# PDB2.net
KiCad netlist of a schematic drawn in EAGLE
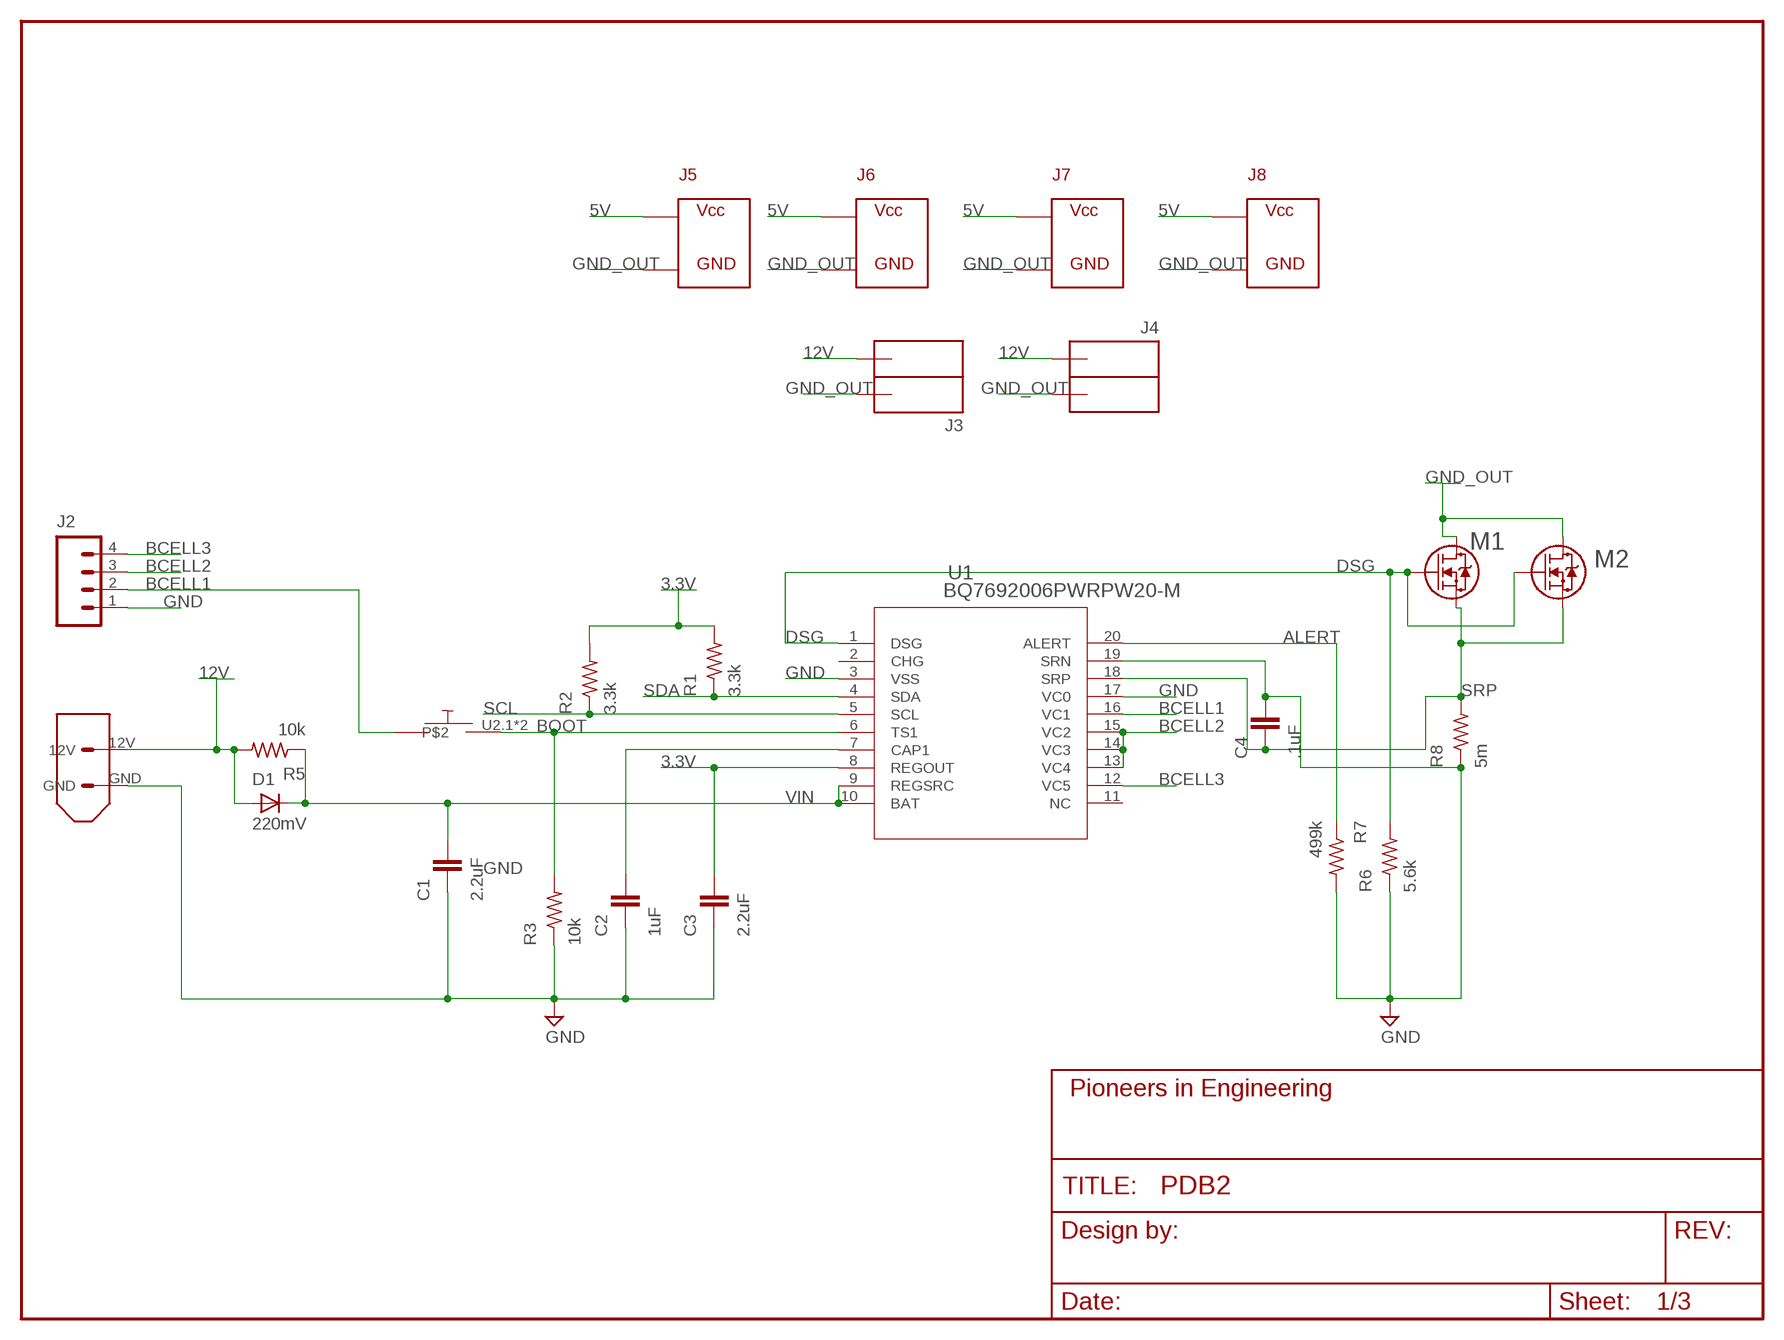
[diagram p0: schematic, sheet 1]
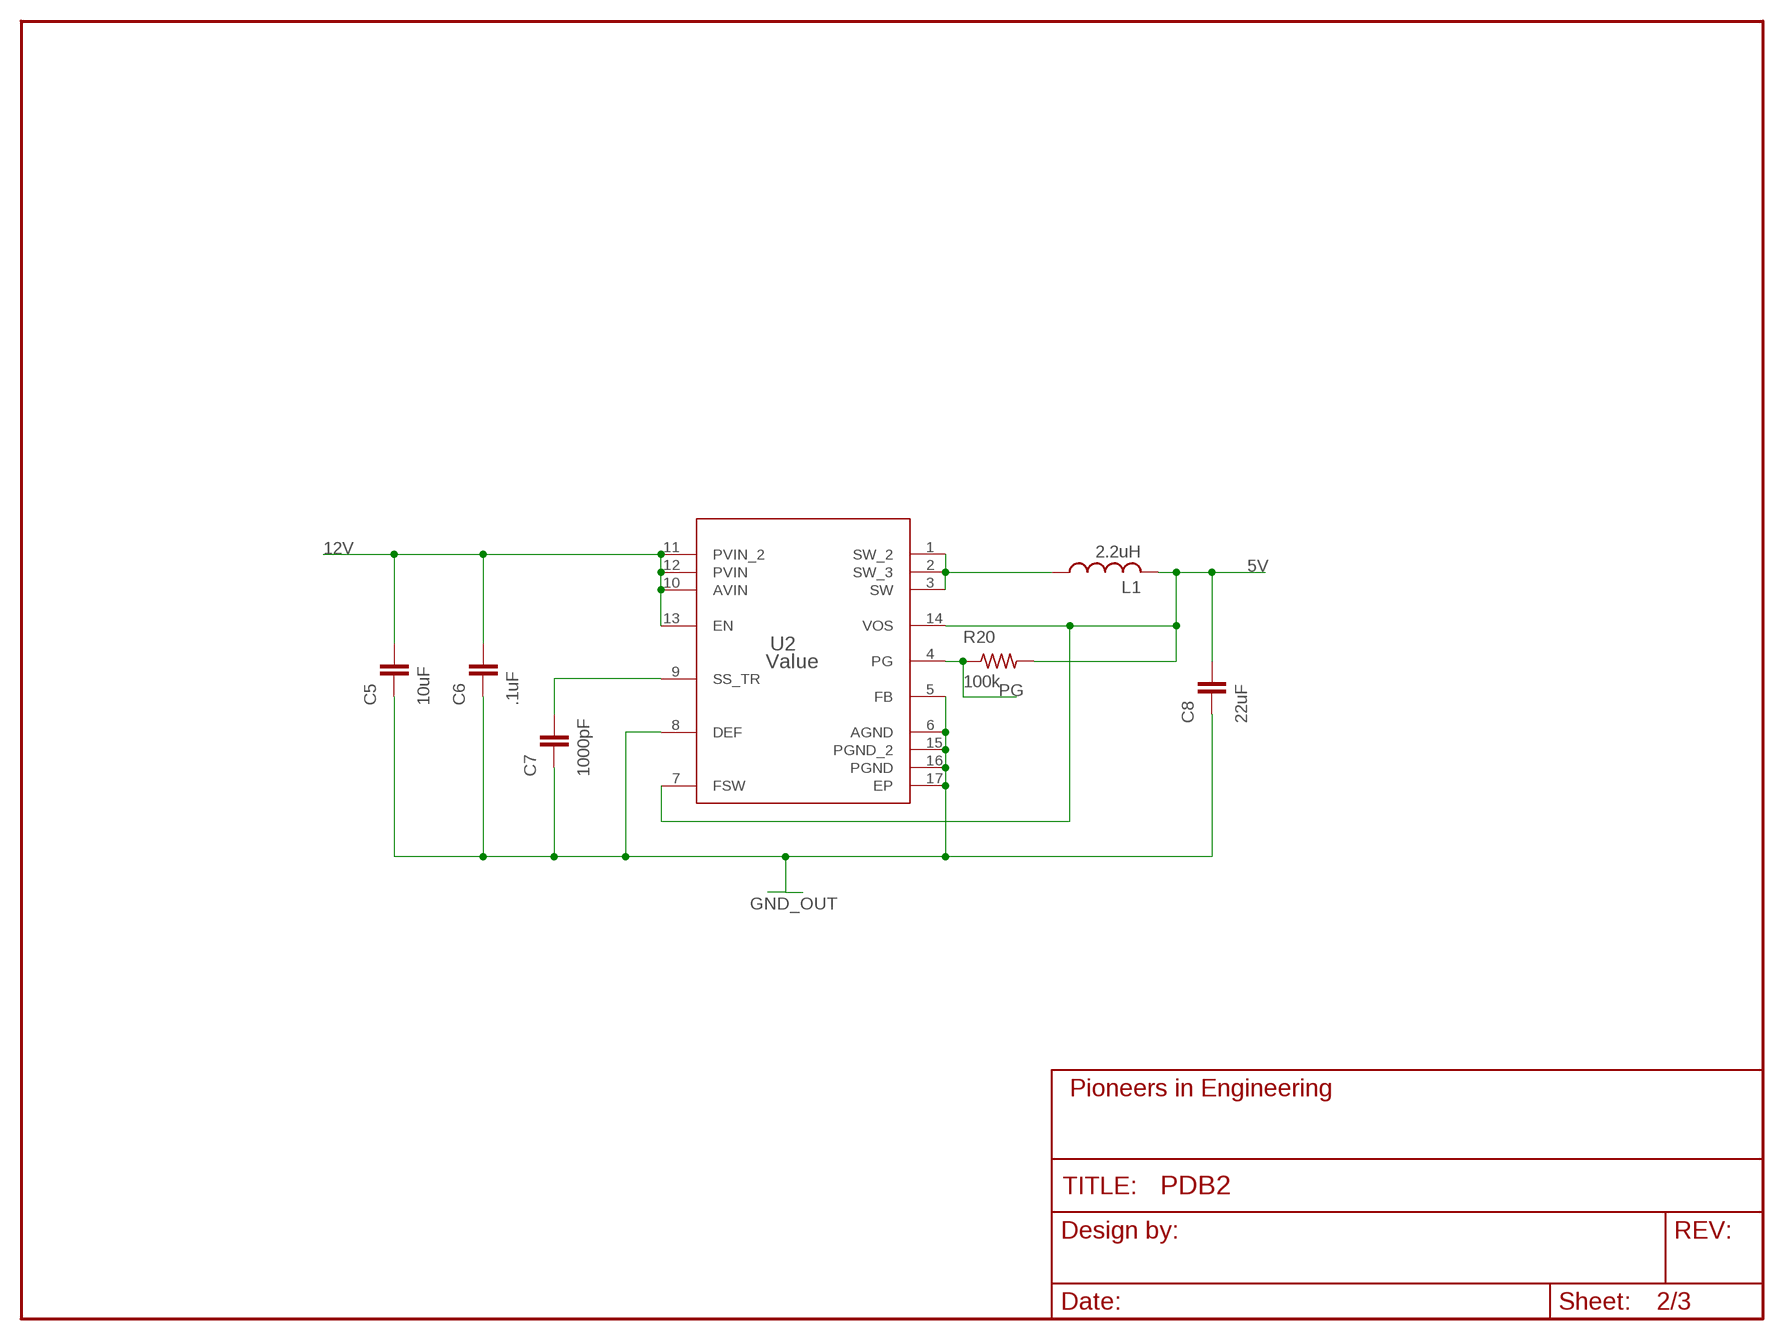
[diagram p1: schematic, sheet 2]
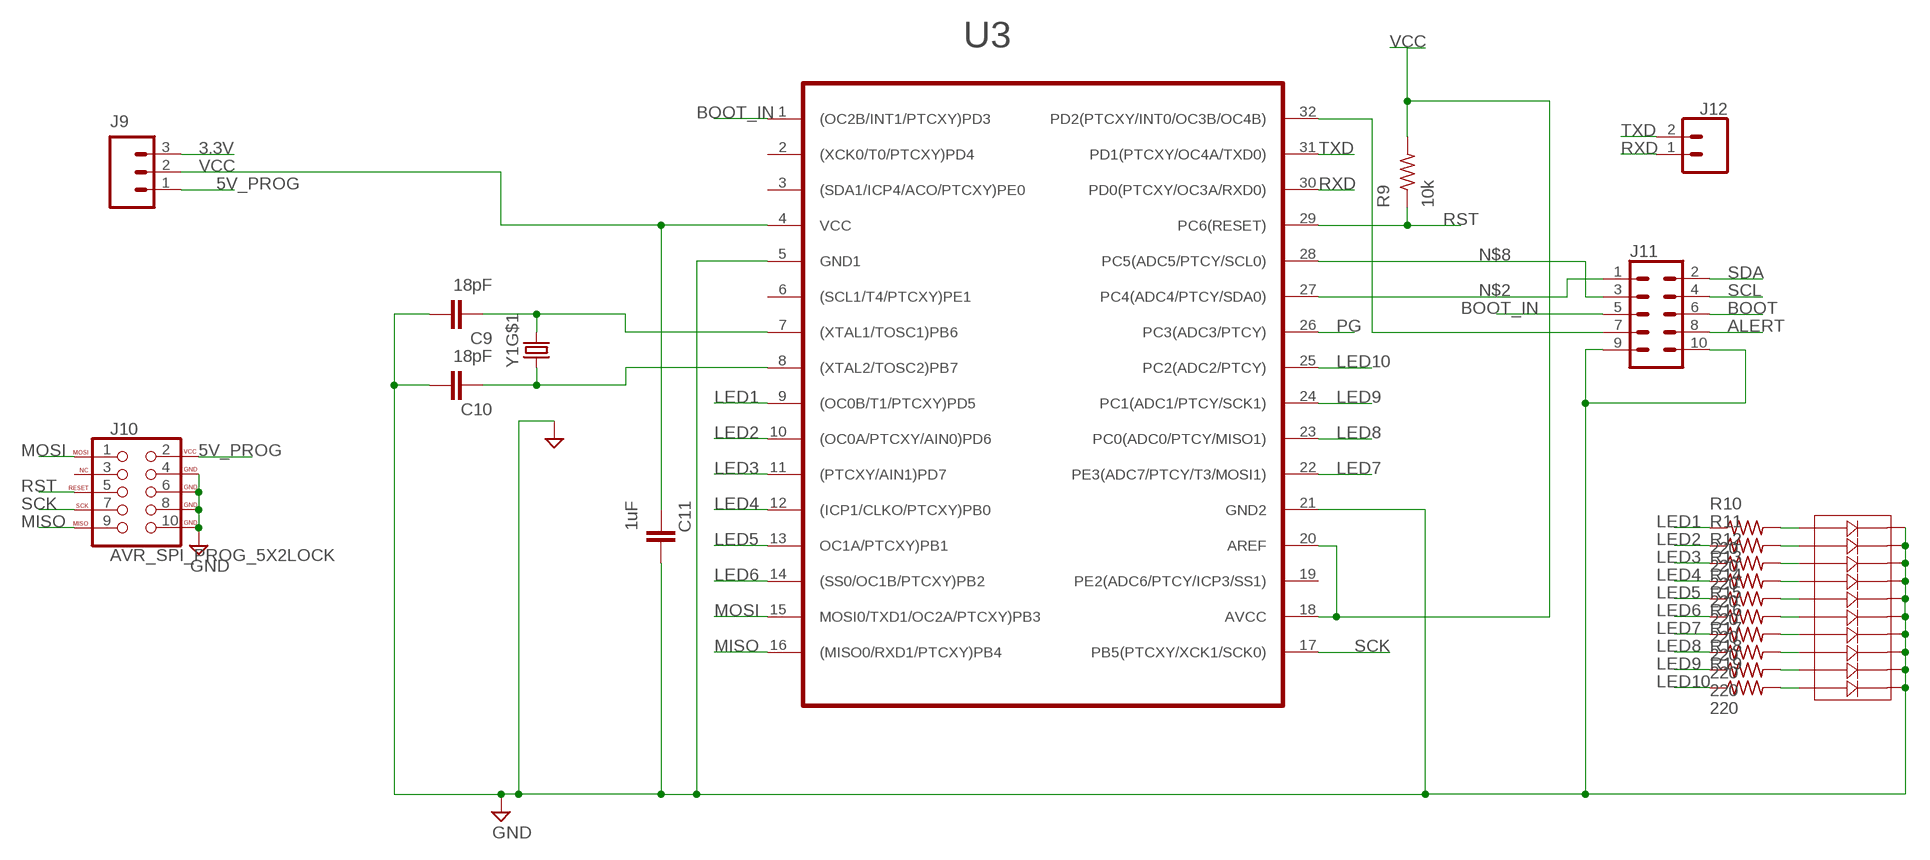
[diagram p2: schematic, sheet 3]

(export (version "E")
  (design (tool "Eeschema 10.0.6"))
  (components
    (comp (ref "BUT1")
      (value "D6C90F1LFS")
      (footprint "eagle-import:D6C_BUTTON")
      (libsource (lib "eagle-import") (part "D6C90F1LFS"))
    )
    (comp (ref "C1")
      (value "2.2uF")
      (footprint "eagle-import:0603-CAP")
      (libsource (lib "eagle-import") (part "CAP0603-CAP"))
    )
    (comp (ref "C2")
      (value "1uF")
      (footprint "eagle-import:0603-CAP")
      (libsource (lib "eagle-import") (part "CAP0603-CAP"))
    )
    (comp (ref "C3")
      (value "2.2uF")
      (footprint "eagle-import:0603-CAP")
      (libsource (lib "eagle-import") (part "CAP0603-CAP"))
    )
    (comp (ref "C4")
      (value ".1uF")
      (footprint "eagle-import:0603-CAP")
      (libsource (lib "eagle-import") (part "CAP0603-CAP"))
    )
    (comp (ref "D1")
      (value "220mV")
      (footprint "eagle-import:SOD-323")
      (libsource (lib "eagle-import") (part "DIODESOD-323"))
    )
    (comp (ref "J1")
      (value "XT60CONNECTOR")
      (footprint "eagle-import:XT60CONNECTOR")
      (fields (field (name "PARTNUMBER") "PRT-10474 "))
      (libsource (lib "eagle-import") (part "XT60CONNECTOR"))
    )
    (comp (ref "J2")
      (value "M041X04-MTA")
      (footprint "eagle-import:1X04-MTA")
      (libsource (lib "eagle-import") (part "M041X04-MTA"))
    )
    (comp (ref "J3")
      (value "ANDERSONVERTICAL")
      (footprint "eagle-import:ANDERSON_VERTICAL")
      (libsource (lib "eagle-import") (part "ANDERSONVERTICAL"))
    )
    (comp (ref "J4")
      (value "ANDERSONVERTICAL")
      (footprint "eagle-import:ANDERSON_VERTICAL")
      (libsource (lib "eagle-import") (part "ANDERSONVERTICAL"))
    )
    (comp (ref "J5")
      (value "ATX")
      (footprint "eagle-import:ATX")
      (libsource (lib "eagle-import") (part "ATX"))
    )
    (comp (ref "J6")
      (value "ATX")
      (footprint "eagle-import:ATX")
      (libsource (lib "eagle-import") (part "ATX"))
    )
    (comp (ref "J7")
      (value "ATX")
      (footprint "eagle-import:ATX")
      (libsource (lib "eagle-import") (part "ATX"))
    )
    (comp (ref "J8")
      (value "ATX")
      (footprint "eagle-import:ATX")
      (libsource (lib "eagle-import") (part "ATX"))
    )
    (comp (ref "M1")
      (value "STD20NF06LDPAK-M")
      (footprint "eagle-import:DPAK-M")
      (fields (field (name "MANUFACTURER_PART_NUMBER") "STD20NF06L"))
      (libsource (lib "eagle-import") (part "STD20NF06LDPAK-M"))
    )
    (comp (ref "M2")
      (value "STD20NF06LDPAK-M")
      (footprint "eagle-import:DPAK-M")
      (fields (field (name "MANUFACTURER_PART_NUMBER") "STD20NF06L"))
      (libsource (lib "eagle-import") (part "STD20NF06LDPAK-M"))
    )
    (comp (ref "R1")
      (value "3.3k")
      (footprint "eagle-import:R0603")
      (fields (field (name "MANUFACTURER") "Rohm Semiconductor"))
      (libsource (lib "eagle-import") (part "R-US_R0603"))
    )
    (comp (ref "R2")
      (value "3.3k")
      (footprint "eagle-import:R0603")
      (fields (field (name "MANUFACTURER") "Rohm Semiconductor"))
      (libsource (lib "eagle-import") (part "R-US_R0603"))
    )
    (comp (ref "R3")
      (value "10k")
      (footprint "eagle-import:R0603")
      (fields (field (name "MANUFACTURER") "Rohm Semiconductor"))
      (libsource (lib "eagle-import") (part "R-US_R0603"))
    )
    (comp (ref "R5")
      (value "10k")
      (footprint "eagle-import:R0603")
      (fields (field (name "MANUFACTURER") "Rohm Semiconductor"))
      (libsource (lib "eagle-import") (part "R-US_R0603"))
    )
    (comp (ref "R6")
      (value "5.6k")
      (footprint "eagle-import:R0603")
      (fields (field (name "MANUFACTURER") "Rohm Semiconductor"))
      (libsource (lib "eagle-import") (part "R-US_R0603"))
    )
    (comp (ref "R7")
      (value "499k")
      (footprint "eagle-import:R0603")
      (fields (field (name "MANUFACTURER") "Rohm Semiconductor"))
      (libsource (lib "eagle-import") (part "R-US_R0603"))
    )
    (comp (ref "R8")
      (value "5m")
      (footprint "eagle-import:SMD_SHUNT")
      (fields (field (name "MANUFACTURER_PART_NO") "WSHM28185L000FEA"))
      (libsource (lib "eagle-import") (part "SHUNT_SMD"))
    )
    (comp (ref "U1")
      (value "BQ7692006PWRPW20-M")
      (footprint "eagle-import:PW20-M")
      (fields (field (name "MANUFACTURER_PART_NUMBER") "BQ7692006PWR"))
      (libsource (lib "eagle-import") (part "BQ7692006PWRPW20-M"))
    )
    (comp (ref "C5")
      (value "10uF")
      (footprint "eagle-import:0805")
      (libsource (lib "eagle-import") (part "CAP0805"))
    )
    (comp (ref "C6")
      (value ".1uF")
      (footprint "eagle-import:0603-CAP")
      (libsource (lib "eagle-import") (part "CAP0603-CAP"))
    )
    (comp (ref "C7")
      (value "1000pF")
      (footprint "eagle-import:0603-CAP")
      (libsource (lib "eagle-import") (part "CAP0603-CAP"))
    )
    (comp (ref "C8")
      (value "22uF")
      (footprint "eagle-import:0805")
      (libsource (lib "eagle-import") (part "CAP0805"))
    )
    (comp (ref "L1")
      (value "2.2uH")
      (footprint "eagle-import:ASPI")
      (libsource (lib "eagle-import") (part "ASPI-0530_INDUCTOR"))
    )
    (comp (ref "R20")
      (value "100k")
      (footprint "eagle-import:R0603")
      (fields (field (name "MANUFACTURER") "Rohm Semiconductor"))
      (libsource (lib "eagle-import") (part "R-US_R0603"))
    )
    (comp (ref "U2")
      (value "Value")
      (footprint "eagle-import:RGT0016C")
      (fields
        (field (name "MANUFACTURER") "Texas Instruments")
        (field (name "MANUFACTURER_PART_NUMBER") "TPS62133RGTR")
      )
      (libsource (lib "eagle-import") (part "TPS62133RGTR"))
    )
    (comp (ref "C9")
      (value "18pF")
      (footprint "eagle-import:0603-CAP")
      (libsource (lib "eagle-import") (part "CAP0603-CAP"))
    )
    (comp (ref "C10")
      (value "18pF")
      (footprint "eagle-import:0603-CAP")
      (libsource (lib "eagle-import") (part "CAP0603-CAP"))
    )
    (comp (ref "C11")
      (value "1uF")
      (footprint "eagle-import:0603-CAP")
      (libsource (lib "eagle-import") (part "CAP0603-CAP"))
    )
    (comp (ref "J9")
      (value "M03PTH")
      (footprint "eagle-import:1X03")
      (libsource (lib "eagle-import") (part "M03PTH"))
    )
    (comp (ref "J10")
      (value "AVR_SPI_PROG_5X2LOCK")
      (footprint "eagle-import:2X5-SHROUDED_LOCK")
      (libsource (lib "eagle-import") (part "AVR_SPI_PROG_5X2LOCK"))
    )
    (comp (ref "J11")
      (value "CONN_05X2NO_SILK")
      (footprint "eagle-import:2X5_NOSILK")
      (libsource (lib "eagle-import") (part "CONN_05X2NO_SILK"))
    )
    (comp (ref "J12")
      (value "CONN_02")
      (footprint "eagle-import:1X02")
      (libsource (lib "eagle-import") (part "CONN_02"))
    )
    (comp (ref "LED1")
      (value "BAR_SEGMENT_DISPLAY")
      (footprint "eagle-import:BAR_SEGMENT_DISPLAY")
      (libsource (lib "eagle-import") (part "BAR_SEGMENT_DISPLAY"))
    )
    (comp (ref "R9")
      (value "10k")
      (footprint "eagle-import:R0603")
      (fields (field (name "MANUFACTURER") "Rohm Semiconductor"))
      (libsource (lib "eagle-import") (part "R-US_R0603"))
    )
    (comp (ref "R10")
      (value "220")
      (footprint "eagle-import:R0603")
      (fields (field (name "MANUFACTURER") "Rohm Semiconductor"))
      (libsource (lib "eagle-import") (part "R-US_R0603"))
    )
    (comp (ref "R11")
      (value "220")
      (footprint "eagle-import:R0603")
      (fields (field (name "MANUFACTURER") "Rohm Semiconductor"))
      (libsource (lib "eagle-import") (part "R-US_R0603"))
    )
    (comp (ref "R12")
      (value "220")
      (footprint "eagle-import:R0603")
      (fields (field (name "MANUFACTURER") "Rohm Semiconductor"))
      (libsource (lib "eagle-import") (part "R-US_R0603"))
    )
    (comp (ref "R13")
      (value "220")
      (footprint "eagle-import:R0603")
      (fields (field (name "MANUFACTURER") "Rohm Semiconductor"))
      (libsource (lib "eagle-import") (part "R-US_R0603"))
    )
    (comp (ref "R14")
      (value "220")
      (footprint "eagle-import:R0603")
      (fields (field (name "MANUFACTURER") "Rohm Semiconductor"))
      (libsource (lib "eagle-import") (part "R-US_R0603"))
    )
    (comp (ref "R15")
      (value "220")
      (footprint "eagle-import:R0603")
      (fields (field (name "MANUFACTURER") "Rohm Semiconductor"))
      (libsource (lib "eagle-import") (part "R-US_R0603"))
    )
    (comp (ref "R16")
      (value "220")
      (footprint "eagle-import:R0603")
      (fields (field (name "MANUFACTURER") "Rohm Semiconductor"))
      (libsource (lib "eagle-import") (part "R-US_R0603"))
    )
    (comp (ref "R17")
      (value "220")
      (footprint "eagle-import:R0603")
      (fields (field (name "MANUFACTURER") "Rohm Semiconductor"))
      (libsource (lib "eagle-import") (part "R-US_R0603"))
    )
    (comp (ref "R18")
      (value "220")
      (footprint "eagle-import:R0603")
      (fields (field (name "MANUFACTURER") "Rohm Semiconductor"))
      (libsource (lib "eagle-import") (part "R-US_R0603"))
    )
    (comp (ref "R19")
      (value "220")
      (footprint "eagle-import:R0603")
      (fields (field (name "MANUFACTURER") "Rohm Semiconductor"))
      (libsource (lib "eagle-import") (part "R-US_R0603"))
    )
    (comp (ref "U3")
      (value "ATMEGA328PB-AU")
      (footprint "eagle-import:TQFP32-08")
      (libsource (lib "eagle-import") (part "ATMEGA328PB-AU"))
    )
    (comp (ref "Y1")
      (value "ECX-53BSMDCRYSTAL")
      (footprint "eagle-import:SMD_CRYSTAL")
      (fields (field (name "MANUFACTURER_PART_NO") "ECS-80-18-30B-AGN-TR"))
      (libsource (lib "eagle-import") (part "ECX-53BSMDCRYSTAL"))
    )
  )
  (nets
    (net (code "1") (name "3.3V") (class "Default")
      (node (ref "C3") (pin "2") (pinfunction "2_2") (pintype "passive"))
      (node (ref "J9") (pin "3") (pinfunction "3_3") (pintype "passive"))
      (node (ref "R1") (pin "2") (pinfunction "2_2") (pintype "passive"))
      (node (ref "R2") (pin "2") (pinfunction "2_2") (pintype "passive"))
      (node (ref "U1") (pin "8") (pinfunction "REGOUT_8") (pintype "power_in"))
    )
    (net (code "2") (name "5V") (class "Default")
      (node (ref "C8") (pin "2") (pinfunction "2_2") (pintype "passive"))
      (node (ref "J5") (pin "P$1") (pinfunction "P$1_P$1") (pintype "power_in"))
      (node (ref "J6") (pin "P$1") (pinfunction "P$1_P$1") (pintype "power_in"))
      (node (ref "J7") (pin "P$1") (pinfunction "P$1_P$1") (pintype "power_in"))
      (node (ref "J8") (pin "P$1") (pinfunction "P$1_P$1") (pintype "power_in"))
      (node (ref "L1") (pin "P$2") (pinfunction "2_P$2") (pintype "passive"))
      (node (ref "R20") (pin "2") (pinfunction "2_2") (pintype "passive"))
      (node (ref "U2") (pin "14") (pinfunction "VOS_14") (pintype "input"))
      (node (ref "U2") (pin "7") (pinfunction "FSW_7") (pintype "input"))
    )
    (net (code "3") (name "5V_PROG") (class "Default")
      (node (ref "J10") (pin "2") (pinfunction "VCC_2") (pintype "power_in"))
      (node (ref "J9") (pin "1") (pinfunction "1_1") (pintype "passive"))
    )
    (net (code "4") (name "12V") (class "Default")
      (node (ref "C5") (pin "2") (pinfunction "2_2") (pintype "passive"))
      (node (ref "C6") (pin "2") (pinfunction "2_2") (pintype "passive"))
      (node (ref "D1") (pin "1") (pinfunction "A_1") (pintype "passive"))
      (node (ref "J1") (pin "12V") (pinfunction "12V_12V") (pintype "bidirectional"))
      (node (ref "J3") (pin "PIN1") (pinfunction "OUTB_PIN1") (pintype "bidirectional"))
      (node (ref "J4") (pin "PIN2") (pinfunction "OUTA_PIN2") (pintype "bidirectional"))
      (node (ref "R5") (pin "2") (pinfunction "2_2") (pintype "passive"))
      (node (ref "U2") (pin "10") (pinfunction "AVIN_10") (pintype "power_in"))
      (node (ref "U2") (pin "11") (pinfunction "PVIN_2_11") (pintype "power_in"))
      (node (ref "U2") (pin "12") (pinfunction "PVIN_12") (pintype "power_in"))
      (node (ref "U2") (pin "13") (pinfunction "EN_13") (pintype "input"))
    )
    (net (code "5") (name "ALERT") (class "Default")
      (node (ref "J11") (pin "8") (pinfunction "8_8") (pintype "passive"))
      (node (ref "R7") (pin "1") (pinfunction "1_1") (pintype "passive"))
      (node (ref "U1") (pin "20") (pinfunction "ALERT_20") (pintype "bidirectional"))
    )
    (net (code "6") (name "BCELL1") (class "Default")
      (node (ref "BUT1") (pin "U1.1") (pinfunction "P$1_U1.1") (pintype "bidirectional"))
      (node (ref "BUT1") (pin "U1.2") (pinfunction "P$1_U1.2") (pintype "bidirectional"))
      (node (ref "J2") (pin "2") (pinfunction "2_2") (pintype "passive"))
      (node (ref "U1") (pin "16") (pinfunction "VC1_16") (pintype "input"))
    )
    (net (code "7") (name "BCELL2") (class "Default")
      (node (ref "J2") (pin "3") (pinfunction "3_3") (pintype "passive"))
      (node (ref "U1") (pin "13") (pinfunction "VC4_13") (pintype "input"))
      (node (ref "U1") (pin "14") (pinfunction "VC3_14") (pintype "input"))
      (node (ref "U1") (pin "15") (pinfunction "VC2_15") (pintype "input"))
    )
    (net (code "8") (name "BCELL3") (class "Default")
      (node (ref "J2") (pin "4") (pinfunction "4_4") (pintype "passive"))
      (node (ref "U1") (pin "12") (pinfunction "VC5_12") (pintype "input"))
    )
    (net (code "9") (name "BOOT") (class "Default")
      (node (ref "BUT1") (pin "U2.1") (pinfunction "P$2_U2.1") (pintype "bidirectional"))
      (node (ref "BUT1") (pin "U2.2") (pinfunction "P$2_U2.2") (pintype "bidirectional"))
      (node (ref "J11") (pin "6") (pinfunction "6_6") (pintype "passive"))
      (node (ref "R3") (pin "2") (pinfunction "2_2") (pintype "passive"))
      (node (ref "U1") (pin "6") (pinfunction "TS1_6") (pintype "input"))
    )
    (net (code "10") (name "BOOT_IN") (class "Default")
      (node (ref "J11") (pin "5") (pinfunction "5_5") (pintype "passive"))
      (node (ref "U3") (pin "1") (pinfunction "(OC2B/INT1/PTCXY)PD3_1") (pintype "bidirectional"))
    )
    (net (code "11") (name "DSG") (class "Default")
      (node (ref "M1") (pin "1") (pinfunction "1_1") (pintype "passive"))
      (node (ref "M2") (pin "1") (pinfunction "1_1") (pintype "passive"))
      (node (ref "R6") (pin "2") (pinfunction "2_2") (pintype "passive"))
      (node (ref "U1") (pin "1") (pinfunction "DSG_1") (pintype "output"))
    )
    (net (code "12") (name "GND") (class "Default")
      (node (ref "C1") (pin "1") (pinfunction "1_1") (pintype "passive"))
      (node (ref "C10") (pin "2") (pinfunction "2_2") (pintype "passive"))
      (node (ref "C11") (pin "2") (pinfunction "2_2") (pintype "passive"))
      (node (ref "C2") (pin "1") (pinfunction "1_1") (pintype "passive"))
      (node (ref "C3") (pin "1") (pinfunction "1_1") (pintype "passive"))
      (node (ref "C4") (pin "2") (pinfunction "2_2") (pintype "passive"))
      (node (ref "C9") (pin "2") (pinfunction "2_2") (pintype "passive"))
      (node (ref "J1") (pin "GND") (pinfunction "GND_GND") (pintype "bidirectional"))
      (node (ref "J10") (pin "10") (pinfunction "GND_10") (pintype "power_in"))
      (node (ref "J10") (pin "4") (pinfunction "GND_4") (pintype "power_in"))
      (node (ref "J10") (pin "6") (pinfunction "GND_6") (pintype "power_in"))
      (node (ref "J10") (pin "8") (pinfunction "GND_8") (pintype "power_in"))
      (node (ref "J11") (pin "10") (pinfunction "10_10") (pintype "passive"))
      (node (ref "J11") (pin "9") (pinfunction "9_9") (pintype "passive"))
      (node (ref "J2") (pin "1") (pinfunction "1_1") (pintype "passive"))
      (node (ref "LED1") (pin "BAR_DISPLAY10") (pinfunction "P11_BAR_DISPLAY10") (pintype "bidirectional"))
      (node (ref "LED1") (pin "BAR_DISPLAY11") (pinfunction "P12_BAR_DISPLAY11") (pintype "bidirectional"))
      (node (ref "LED1") (pin "BAR_DISPLAY12") (pinfunction "P13_BAR_DISPLAY12") (pintype "bidirectional"))
      (node (ref "LED1") (pin "BAR_DISPLAY13") (pinfunction "P14_BAR_DISPLAY13") (pintype "bidirectional"))
      (node (ref "LED1") (pin "BAR_DISPLAY14") (pinfunction "P15_BAR_DISPLAY14") (pintype "bidirectional"))
      (node (ref "LED1") (pin "BAR_DISPLAY15") (pinfunction "P16_BAR_DISPLAY15") (pintype "bidirectional"))
      (node (ref "LED1") (pin "BAR_DISPLAY16") (pinfunction "P17_BAR_DISPLAY16") (pintype "bidirectional"))
      (node (ref "LED1") (pin "BAR_DISPLAY17") (pinfunction "P18_BAR_DISPLAY17") (pintype "bidirectional"))
      (node (ref "LED1") (pin "BAR_DISPLAY18") (pinfunction "P19_BAR_DISPLAY18") (pintype "bidirectional"))
      (node (ref "LED1") (pin "BAR_DISPLAY19") (pinfunction "P20_BAR_DISPLAY19") (pintype "bidirectional"))
      (node (ref "R3") (pin "1") (pinfunction "1_1") (pintype "passive"))
      (node (ref "R6") (pin "1") (pinfunction "1_1") (pintype "passive"))
      (node (ref "R7") (pin "2") (pinfunction "2_2") (pintype "passive"))
      (node (ref "R8") (pin "P$1") (pinfunction "1_P$1") (pintype "passive"))
      (node (ref "U1") (pin "17") (pinfunction "VC0_17") (pintype "input"))
      (node (ref "U1") (pin "19") (pinfunction "SRN_19") (pintype "input"))
      (node (ref "U1") (pin "3") (pinfunction "VSS_3") (pintype "power_in"))
      (node (ref "U3") (pin "21") (pinfunction "GND2_21") (pintype "bidirectional"))
      (node (ref "U3") (pin "5") (pinfunction "GND1_5") (pintype "bidirectional"))
      (node (ref "Y1") (pin "P1") (pinfunction "GND_P1") (pintype "power_in"))
      (node (ref "Y1") (pin "P3") (pinfunction "GND_P3") (pintype "power_in"))
    )
    (net (code "13") (name "GND_OUT") (class "Default")
      (node (ref "C5") (pin "1") (pinfunction "1_1") (pintype "passive"))
      (node (ref "C6") (pin "1") (pinfunction "1_1") (pintype "passive"))
      (node (ref "C7") (pin "1") (pinfunction "1_1") (pintype "passive"))
      (node (ref "C8") (pin "1") (pinfunction "1_1") (pintype "passive"))
      (node (ref "J3") (pin "PIN2") (pinfunction "OUTA_PIN2") (pintype "bidirectional"))
      (node (ref "J4") (pin "PIN1") (pinfunction "OUTB_PIN1") (pintype "bidirectional"))
      (node (ref "J5") (pin "P$2") (pinfunction "P$2_P$2") (pintype "power_in"))
      (node (ref "J6") (pin "P$2") (pinfunction "P$2_P$2") (pintype "power_in"))
      (node (ref "J7") (pin "P$2") (pinfunction "P$2_P$2") (pintype "power_in"))
      (node (ref "J8") (pin "P$2") (pinfunction "P$2_P$2") (pintype "power_in"))
      (node (ref "M1") (pin "3") (pinfunction "2_3") (pintype "passive"))
      (node (ref "M2") (pin "3") (pinfunction "2_3") (pintype "passive"))
      (node (ref "U2") (pin "15") (pinfunction "PGND_2_15") (pintype "power_in"))
      (node (ref "U2") (pin "16") (pinfunction "PGND_16") (pintype "power_in"))
      (node (ref "U2") (pin "17") (pinfunction "EP_17") (pintype "power_in"))
      (node (ref "U2") (pin "5") (pinfunction "FB_5") (pintype "input"))
      (node (ref "U2") (pin "6") (pinfunction "AGND_6") (pintype "power_in"))
      (node (ref "U2") (pin "8") (pinfunction "DEF_8") (pintype "input"))
    )
    (net (code "14") (name "LED1") (class "Default")
      (node (ref "R10") (pin "1") (pinfunction "1_1") (pintype "passive"))
      (node (ref "U3") (pin "9") (pinfunction "(OC0B/T1/PTCXY)PD5_9") (pintype "bidirectional"))
    )
    (net (code "15") (name "LED2") (class "Default")
      (node (ref "R11") (pin "1") (pinfunction "1_1") (pintype "passive"))
      (node (ref "U3") (pin "10") (pinfunction "(OC0A/PTCXY/AIN0)PD6_10") (pintype "bidirectional"))
    )
    (net (code "16") (name "LED3") (class "Default")
      (node (ref "R12") (pin "1") (pinfunction "1_1") (pintype "passive"))
      (node (ref "U3") (pin "11") (pinfunction "(PTCXY/AIN1)PD7_11") (pintype "bidirectional"))
    )
    (net (code "17") (name "LED4") (class "Default")
      (node (ref "R13") (pin "1") (pinfunction "1_1") (pintype "passive"))
      (node (ref "U3") (pin "12") (pinfunction "(ICP1/CLKO/PTCXY)PB0_12") (pintype "bidirectional"))
    )
    (net (code "18") (name "LED5") (class "Default")
      (node (ref "R14") (pin "1") (pinfunction "1_1") (pintype "passive"))
      (node (ref "U3") (pin "13") (pinfunction "OC1A/PTCXY)PB1_13") (pintype "bidirectional"))
    )
    (net (code "19") (name "LED6") (class "Default")
      (node (ref "R15") (pin "1") (pinfunction "1_1") (pintype "passive"))
      (node (ref "U3") (pin "14") (pinfunction "(SS0/OC1B/PTCXY)PB2_14") (pintype "bidirectional"))
    )
    (net (code "20") (name "LED7") (class "Default")
      (node (ref "R16") (pin "1") (pinfunction "1_1") (pintype "passive"))
      (node (ref "U3") (pin "22") (pinfunction "PE3(ADC7/PTCY/T3/MOSI1)_22") (pintype "bidirectional"))
    )
    (net (code "21") (name "LED8") (class "Default")
      (node (ref "R17") (pin "1") (pinfunction "1_1") (pintype "passive"))
      (node (ref "U3") (pin "23") (pinfunction "PC0(ADC0/PTCY/MISO1)_23") (pintype "bidirectional"))
    )
    (net (code "22") (name "LED9") (class "Default")
      (node (ref "R18") (pin "1") (pinfunction "1_1") (pintype "passive"))
      (node (ref "U3") (pin "24") (pinfunction "PC1(ADC1/PTCY/SCK1)_24") (pintype "bidirectional"))
    )
    (net (code "23") (name "LED10") (class "Default")
      (node (ref "R19") (pin "1") (pinfunction "1_1") (pintype "passive"))
      (node (ref "U3") (pin "25") (pinfunction "PC2(ADC2/PTCY)_25") (pintype "bidirectional"))
    )
    (net (code "24") (name "MISO") (class "Default")
      (node (ref "J10") (pin "9") (pinfunction "MISO_9") (pintype "passive"))
      (node (ref "U3") (pin "16") (pinfunction "(MISO0/RXD1/PTCXY)PB4_16") (pintype "bidirectional"))
    )
    (net (code "25") (name "MOSI") (class "Default")
      (node (ref "J10") (pin "1") (pinfunction "MOSI_1") (pintype "passive"))
      (node (ref "U3") (pin "15") (pinfunction "MOSI0/TXD1/OC2A/PTCXY)PB3_15") (pintype "bidirectional"))
    )
    (net (code "26") (name "N$2") (class "Default")
      (node (ref "J11") (pin "1") (pinfunction "1_1") (pintype "passive"))
      (node (ref "U3") (pin "27") (pinfunction "PC4(ADC4/PTCY/SDA0)_27") (pintype "bidirectional"))
    )
    (net (code "27") (name "N$8") (class "Default")
      (node (ref "J11") (pin "3") (pinfunction "3_3") (pintype "passive"))
      (node (ref "U3") (pin "28") (pinfunction "PC5(ADC5/PTCY/SCL0)_28") (pintype "bidirectional"))
    )
    (net (code "28") (name "Net-(L1-1)") (class "Default")
      (node (ref "L1") (pin "P$1") (pinfunction "1_P$1") (pintype "passive"))
      (node (ref "U2") (pin "1") (pinfunction "SW_2_1") (pintype "power_in"))
      (node (ref "U2") (pin "2") (pinfunction "SW_3_2") (pintype "power_in"))
      (node (ref "U2") (pin "3") (pinfunction "SW_3") (pintype "power_in"))
    )
    (net (code "29") (name "Net-(LED1-P1)") (class "Default")
      (node (ref "LED1") (pin "BAR_DISPLAY0") (pinfunction "P1_BAR_DISPLAY0") (pintype "bidirectional"))
      (node (ref "R10") (pin "2") (pinfunction "2_2") (pintype "passive"))
    )
    (net (code "30") (name "Net-(LED1-P2)") (class "Default")
      (node (ref "LED1") (pin "BAR_DISPLAY1") (pinfunction "P2_BAR_DISPLAY1") (pintype "bidirectional"))
      (node (ref "R11") (pin "2") (pinfunction "2_2") (pintype "passive"))
    )
    (net (code "31") (name "Net-(LED1-P3)") (class "Default")
      (node (ref "LED1") (pin "BAR_DISPLAY2") (pinfunction "P3_BAR_DISPLAY2") (pintype "bidirectional"))
      (node (ref "R12") (pin "2") (pinfunction "2_2") (pintype "passive"))
    )
    (net (code "32") (name "Net-(LED1-P4)") (class "Default")
      (node (ref "LED1") (pin "BAR_DISPLAY3") (pinfunction "P4_BAR_DISPLAY3") (pintype "bidirectional"))
      (node (ref "R13") (pin "2") (pinfunction "2_2") (pintype "passive"))
    )
    (net (code "33") (name "Net-(LED1-P5)") (class "Default")
      (node (ref "LED1") (pin "BAR_DISPLAY4") (pinfunction "P5_BAR_DISPLAY4") (pintype "bidirectional"))
      (node (ref "R14") (pin "2") (pinfunction "2_2") (pintype "passive"))
    )
    (net (code "34") (name "Net-(LED1-P6)") (class "Default")
      (node (ref "LED1") (pin "BAR_DISPLAY5") (pinfunction "P6_BAR_DISPLAY5") (pintype "bidirectional"))
      (node (ref "R15") (pin "2") (pinfunction "2_2") (pintype "passive"))
    )
    (net (code "35") (name "Net-(LED1-P7)") (class "Default")
      (node (ref "LED1") (pin "BAR_DISPLAY6") (pinfunction "P7_BAR_DISPLAY6") (pintype "bidirectional"))
      (node (ref "R16") (pin "2") (pinfunction "2_2") (pintype "passive"))
    )
    (net (code "36") (name "Net-(LED1-P8)") (class "Default")
      (node (ref "LED1") (pin "BAR_DISPLAY7") (pinfunction "P8_BAR_DISPLAY7") (pintype "bidirectional"))
      (node (ref "R17") (pin "2") (pinfunction "2_2") (pintype "passive"))
    )
    (net (code "37") (name "Net-(LED1-P9)") (class "Default")
      (node (ref "LED1") (pin "BAR_DISPLAY8") (pinfunction "P9_BAR_DISPLAY8") (pintype "bidirectional"))
      (node (ref "R18") (pin "2") (pinfunction "2_2") (pintype "passive"))
    )
    (net (code "38") (name "Net-(LED1-P10)") (class "Default")
      (node (ref "LED1") (pin "BAR_DISPLAY9") (pinfunction "P10_BAR_DISPLAY9") (pintype "bidirectional"))
      (node (ref "R19") (pin "2") (pinfunction "2_2") (pintype "passive"))
    )
    (net (code "39") (name "Net-(U1-CAP1)") (class "Default")
      (node (ref "C2") (pin "2") (pinfunction "2_2") (pintype "passive"))
      (node (ref "U1") (pin "7") (pinfunction "CAP1_7") (pintype "output"))
    )
    (net (code "40") (name "Net-(U2-SS_TR)") (class "Default")
      (node (ref "C7") (pin "2") (pinfunction "2_2") (pintype "passive"))
      (node (ref "U2") (pin "9") (pinfunction "SS_TR_9") (pintype "input"))
    )
    (net (code "41") (name "Net-(U3-(XTAL1{slash}TOSC1)PB6)") (class "Default")
      (node (ref "C9") (pin "1") (pinfunction "1_1") (pintype "passive"))
      (node (ref "U3") (pin "7") (pinfunction "(XTAL1/TOSC1)PB6_7") (pintype "bidirectional"))
      (node (ref "Y1") (pin "P2") (pinfunction "2_P2") (pintype "passive"))
    )
    (net (code "42") (name "Net-(U3-(XTAL2{slash}TOSC2)PB7)") (class "Default")
      (node (ref "C10") (pin "1") (pinfunction "1_1") (pintype "passive"))
      (node (ref "U3") (pin "8") (pinfunction "(XTAL2/TOSC2)PB7_8") (pintype "bidirectional"))
      (node (ref "Y1") (pin "P0") (pinfunction "1_P0") (pintype "passive"))
    )
    (net (code "43") (name "Net-(U3-PD2(PTCXY{slash}INT0{slash}OC3B{slash}OC4B))") (class "Default")
      (node (ref "J11") (pin "7") (pinfunction "7_7") (pintype "passive"))
      (node (ref "U3") (pin "32") (pinfunction "PD2(PTCXY/INT0/OC3B/OC4B)_32") (pintype "bidirectional"))
    )
    (net (code "44") (name "PG") (class "Default")
      (node (ref "R20") (pin "1") (pinfunction "1_1") (pintype "passive"))
      (node (ref "U2") (pin "4") (pinfunction "PG_4") (pintype "open_collector"))
      (node (ref "U3") (pin "26") (pinfunction "PC3(ADC3/PTCY)_26") (pintype "bidirectional"))
    )
    (net (code "45") (name "RST") (class "Default")
      (node (ref "J10") (pin "5") (pinfunction "RESET_5") (pintype "passive"))
      (node (ref "R9") (pin "1") (pinfunction "1_1") (pintype "passive"))
      (node (ref "U3") (pin "29") (pinfunction "PC6(RESET)_29") (pintype "bidirectional"))
    )
    (net (code "46") (name "RXD") (class "Default")
      (node (ref "J12") (pin "1") (pinfunction "1_1") (pintype "passive"))
      (node (ref "U3") (pin "30") (pinfunction "PD0(PTCXY/OC3A/RXD0)_30") (pintype "bidirectional"))
    )
    (net (code "47") (name "SCK") (class "Default")
      (node (ref "J10") (pin "7") (pinfunction "SCK_7") (pintype "passive"))
      (node (ref "U3") (pin "17") (pinfunction "PB5(PTCXY/XCK1/SCK0)_17") (pintype "bidirectional"))
    )
    (net (code "48") (name "SCL") (class "Default")
      (node (ref "J11") (pin "4") (pinfunction "4_4") (pintype "passive"))
      (node (ref "R2") (pin "1") (pinfunction "1_1") (pintype "passive"))
      (node (ref "U1") (pin "5") (pinfunction "SCL_5") (pintype "input"))
    )
    (net (code "49") (name "SDA") (class "Default")
      (node (ref "J11") (pin "2") (pinfunction "2_2") (pintype "passive"))
      (node (ref "R1") (pin "1") (pinfunction "1_1") (pintype "passive"))
      (node (ref "U1") (pin "4") (pinfunction "SDA_4") (pintype "bidirectional"))
    )
    (net (code "50") (name "SRP") (class "Default")
      (node (ref "C4") (pin "1") (pinfunction "1_1") (pintype "passive"))
      (node (ref "M1") (pin "2") (pinfunction "3_2") (pintype "passive"))
      (node (ref "M2") (pin "2") (pinfunction "3_2") (pintype "passive"))
      (node (ref "R8") (pin "P$2") (pinfunction "2_P$2") (pintype "passive"))
      (node (ref "U1") (pin "18") (pinfunction "SRP_18") (pintype "input"))
    )
    (net (code "51") (name "TXD") (class "Default")
      (node (ref "J12") (pin "2") (pinfunction "2_2") (pintype "passive"))
      (node (ref "U3") (pin "31") (pinfunction "PD1(PTCXY/OC4A/TXD0)_31") (pintype "bidirectional"))
    )
    (net (code "52") (name "VCC") (class "Default")
      (node (ref "C11") (pin "1") (pinfunction "1_1") (pintype "passive"))
      (node (ref "J9") (pin "2") (pinfunction "2_2") (pintype "passive"))
      (node (ref "R9") (pin "2") (pinfunction "2_2") (pintype "passive"))
      (node (ref "U3") (pin "18") (pinfunction "AVCC_18") (pintype "bidirectional"))
      (node (ref "U3") (pin "20") (pinfunction "AREF_20") (pintype "bidirectional"))
      (node (ref "U3") (pin "4") (pinfunction "VCC_4") (pintype "bidirectional"))
    )
    (net (code "53") (name "VIN") (class "Default")
      (node (ref "C1") (pin "2") (pinfunction "2_2") (pintype "passive"))
      (node (ref "D1") (pin "2") (pinfunction "C_2") (pintype "passive"))
      (node (ref "R5") (pin "1") (pinfunction "1_1") (pintype "passive"))
      (node (ref "U1") (pin "10") (pinfunction "BAT_10") (pintype "power_in"))
      (node (ref "U1") (pin "9") (pinfunction "REGSRC_9") (pintype "input"))
    )
    (net (code "54") (name "unconnected-(J10-NC-Pad3)") (class "Default")
      (node (ref "J10") (pin "3") (pinfunction "NC_3") (pintype "no_connect"))
    )
    (net (code "55") (name "unconnected-(U1-CHG-Pad2)") (class "Default")
      (node (ref "U1") (pin "2") (pinfunction "CHG_2") (pintype "output"))
    )
    (net (code "56") (name "unconnected-(U1-NC-Pad11)") (class "Default")
      (node (ref "U1") (pin "11") (pinfunction "NC_11") (pintype "no_connect"))
    )
    (net (code "57") (name "unconnected-(U3-(SCL1{slash}T4{slash}PTCXY)PE1-Pad6)") (class "Default")
      (node (ref "U3") (pin "6") (pinfunction "(SCL1/T4/PTCXY)PE1_6") (pintype "bidirectional"))
    )
    (net (code "58") (name "unconnected-(U3-(SDA1{slash}ICP4{slash}ACO{slash}PTCXY)PE0-Pad3)") (class "Default")
      (node (ref "U3") (pin "3") (pinfunction "(SDA1/ICP4/ACO/PTCXY)PE0_3") (pintype "bidirectional"))
    )
    (net (code "59") (name "unconnected-(U3-(XCK0{slash}T0{slash}PTCXY)PD4-Pad2)") (class "Default")
      (node (ref "U3") (pin "2") (pinfunction "(XCK0/T0/PTCXY)PD4_2") (pintype "bidirectional"))
    )
    (net (code "60") (name "unconnected-(U3-PE2(ADC6{slash}PTCY{slash}ICP3{slash}SS1)-Pad19)") (class "Default")
      (node (ref "U3") (pin "19") (pinfunction "PE2(ADC6/PTCY/ICP3/SS1)_19") (pintype "bidirectional"))
    )
  )
)
